# T-11_Version_7.net
KiCad netlist of a schematic drawn in EAGLE
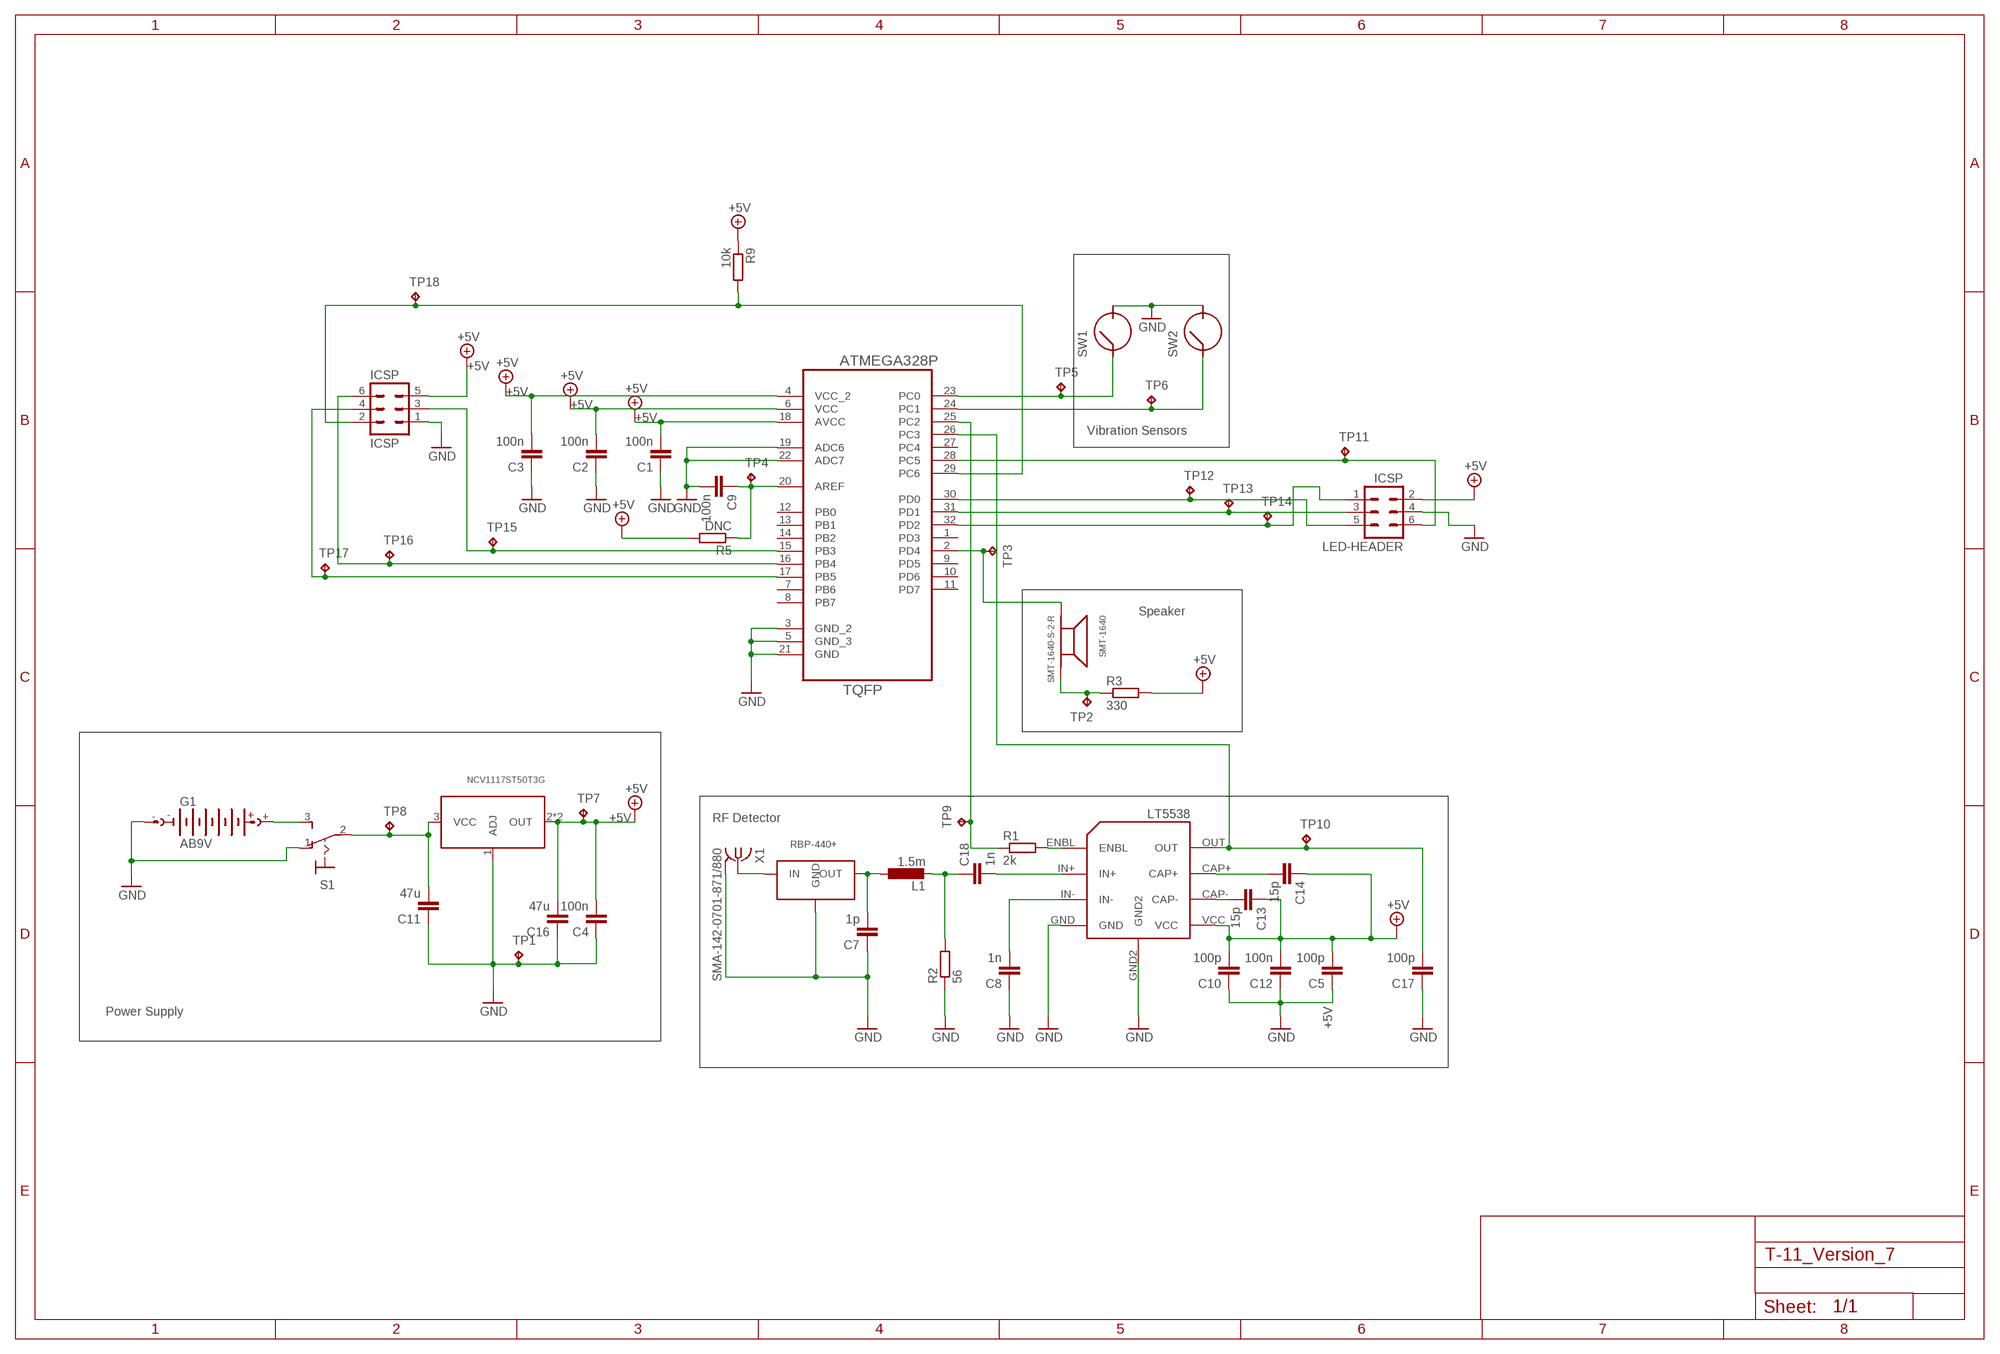
[diagram p0: schematic, sheet 1]

(export (version "E")
  (design (tool "Eeschema 10.0.6"))
  (components
    (comp (ref "C1")
      (value "100n")
      (footprint "eagle-import:C0805")
      (libsource (lib "eagle-import") (part "C-EUC0805"))
    )
    (comp (ref "C2")
      (value "100n")
      (footprint "eagle-import:C0805")
      (libsource (lib "eagle-import") (part "C-EUC0805"))
    )
    (comp (ref "C3")
      (value "100n")
      (footprint "eagle-import:C0805")
      (libsource (lib "eagle-import") (part "C-EUC0805"))
    )
    (comp (ref "C4")
      (value "100n")
      (footprint "eagle-import:C0805")
      (libsource (lib "eagle-import") (part "C-EUC0805"))
    )
    (comp (ref "C5")
      (value "100p")
      (footprint "eagle-import:C0805")
      (libsource (lib "eagle-import") (part "C-EUC0805"))
    )
    (comp (ref "C7")
      (value "1p")
      (footprint "eagle-import:C0805")
      (libsource (lib "eagle-import") (part "C-EUC0805"))
    )
    (comp (ref "C8")
      (value "1n")
      (footprint "eagle-import:C0805")
      (libsource (lib "eagle-import") (part "C-EUC0805"))
    )
    (comp (ref "C9")
      (value "100n")
      (footprint "eagle-import:C0805")
      (libsource (lib "eagle-import") (part "C-EUC0805"))
    )
    (comp (ref "C10")
      (value "100p")
      (footprint "eagle-import:C0805")
      (libsource (lib "eagle-import") (part "C-EUC0805"))
    )
    (comp (ref "C11")
      (value "47u")
      (footprint "eagle-import:C0805")
      (libsource (lib "eagle-import") (part "C-EUC0805"))
    )
    (comp (ref "C12")
      (value "100n")
      (footprint "eagle-import:C0805")
      (libsource (lib "eagle-import") (part "C-EUC0805"))
    )
    (comp (ref "C13")
      (value "15p")
      (footprint "eagle-import:C0805")
      (libsource (lib "eagle-import") (part "C-EUC0805"))
    )
    (comp (ref "C14")
      (value "15p")
      (footprint "eagle-import:C0805")
      (libsource (lib "eagle-import") (part "C-EUC0805"))
    )
    (comp (ref "C16")
      (value "47u")
      (footprint "eagle-import:C0805")
      (libsource (lib "eagle-import") (part "C-EUC0805"))
    )
    (comp (ref "C17")
      (value "100p")
      (footprint "eagle-import:C0805")
      (libsource (lib "eagle-import") (part "C-EUC0805"))
    )
    (comp (ref "C18")
      (value "1n")
      (footprint "eagle-import:C0805")
      (libsource (lib "eagle-import") (part "C-EUC0805"))
    )
    (comp (ref "G1")
      (value "AB9V")
      (footprint "eagle-import:AB9V")
      (libsource (lib "eagle-import") (part "AB9V"))
    )
    (comp (ref "ICSP")
      (value "ICSP")
      (footprint "eagle-import:MA03-2")
      (libsource (lib "eagle-import") (part "MA03-2"))
    )
    (comp (ref "L1")
      (value "1.5m")
      (footprint "eagle-import:L2825P")
      (libsource (lib "eagle-import") (part "L-EUL2825P"))
    )
    (comp (ref "LED-HEADER")
      (value "ICSP")
      (footprint "eagle-import:MA03-2")
      (libsource (lib "eagle-import") (part "MA03-2"))
    )
    (comp (ref "LT5538")
      (value "LT5538")
      (footprint "eagle-import:LT5538")
      (libsource (lib "eagle-import") (part "LT5538"))
    )
    (comp (ref "NVC1")
      (value "NCV1117ST50T3G")
      (footprint "eagle-import:SOT223")
      (libsource (lib "eagle-import") (part "NCV1117ST50T3G"))
    )
    (comp (ref "R1")
      (value "2k")
      (footprint "eagle-import:R0805")
      (libsource (lib "eagle-import") (part "R-EU_R0805"))
    )
    (comp (ref "R2")
      (value "56")
      (footprint "eagle-import:R0805")
      (libsource (lib "eagle-import") (part "R-EU_R0805"))
    )
    (comp (ref "R3")
      (value "330")
      (footprint "eagle-import:R0805")
      (libsource (lib "eagle-import") (part "R-EU_R0805"))
    )
    (comp (ref "R5")
      (value "DNC")
      (footprint "eagle-import:R0805")
      (libsource (lib "eagle-import") (part "R-EU_R0805"))
    )
    (comp (ref "R9")
      (value "10k")
      (footprint "eagle-import:R0805")
      (libsource (lib "eagle-import") (part "R-EU_R0805"))
    )
    (comp (ref "RBP-440+")
      (value "RBP-440+")
      (footprint "eagle-import:GP731")
      (libsource (lib "eagle-import") (part "RBP-440+"))
    )
    (comp (ref "S1")
      (value "320-916")
      (footprint "eagle-import:320-916")
      (libsource (lib "eagle-import") (part "320-916"))
    )
    (comp (ref "SMT-1640")
      (value "SMT-1640-S-2-R")
      (footprint "eagle-import:SMT-1640")
      (libsource (lib "eagle-import") (part "SMT-1640-S-2-R"))
    )
    (comp (ref "SW1")
      (value "SW-1801X")
      (footprint "eagle-import:SW-1801X")
      (libsource (lib "eagle-import") (part "SW-1801X"))
    )
    (comp (ref "SW2")
      (value "SW-1801X")
      (footprint "eagle-import:SW-1801X")
      (libsource (lib "eagle-import") (part "SW-1801X"))
    )
    (comp (ref "TP1")
      (value "TPTP10R")
      (footprint "eagle-import:TP10R")
      (libsource (lib "eagle-import") (part "TPTP10R"))
    )
    (comp (ref "TP2")
      (value "TPTP10R")
      (footprint "eagle-import:TP10R")
      (libsource (lib "eagle-import") (part "TPTP10R"))
    )
    (comp (ref "TP3")
      (value "TPTP10R")
      (footprint "eagle-import:TP10R")
      (libsource (lib "eagle-import") (part "TPTP10R"))
    )
    (comp (ref "TP4")
      (value "TPTP10R")
      (footprint "eagle-import:TP10R")
      (libsource (lib "eagle-import") (part "TPTP10R"))
    )
    (comp (ref "TP5")
      (value "TPTP10R")
      (footprint "eagle-import:TP10R")
      (libsource (lib "eagle-import") (part "TPTP10R"))
    )
    (comp (ref "TP6")
      (value "TPTP10R")
      (footprint "eagle-import:TP10R")
      (libsource (lib "eagle-import") (part "TPTP10R"))
    )
    (comp (ref "TP7")
      (value "TPTP10R")
      (footprint "eagle-import:TP10R")
      (libsource (lib "eagle-import") (part "TPTP10R"))
    )
    (comp (ref "TP8")
      (value "TPTP10R")
      (footprint "eagle-import:TP10R")
      (libsource (lib "eagle-import") (part "TPTP10R"))
    )
    (comp (ref "TP9")
      (value "TPTP10R")
      (footprint "eagle-import:TP10R")
      (libsource (lib "eagle-import") (part "TPTP10R"))
    )
    (comp (ref "TP10")
      (value "TPTP10R")
      (footprint "eagle-import:TP10R")
      (libsource (lib "eagle-import") (part "TPTP10R"))
    )
    (comp (ref "TP11")
      (value "TPTP10R")
      (footprint "eagle-import:TP10R")
      (libsource (lib "eagle-import") (part "TPTP10R"))
    )
    (comp (ref "TP12")
      (value "TPTP10R")
      (footprint "eagle-import:TP10R")
      (libsource (lib "eagle-import") (part "TPTP10R"))
    )
    (comp (ref "TP13")
      (value "TPTP10R")
      (footprint "eagle-import:TP10R")
      (libsource (lib "eagle-import") (part "TPTP10R"))
    )
    (comp (ref "TP14")
      (value "TPTP10R")
      (footprint "eagle-import:TP10R")
      (libsource (lib "eagle-import") (part "TPTP10R"))
    )
    (comp (ref "TP15")
      (value "TPTP10R")
      (footprint "eagle-import:TP10R")
      (libsource (lib "eagle-import") (part "TPTP10R"))
    )
    (comp (ref "TP16")
      (value "TPTP10R")
      (footprint "eagle-import:TP10R")
      (libsource (lib "eagle-import") (part "TPTP10R"))
    )
    (comp (ref "TP17")
      (value "TPTP10R")
      (footprint "eagle-import:TP10R")
      (libsource (lib "eagle-import") (part "TPTP10R"))
    )
    (comp (ref "TP18")
      (value "TPTP10R")
      (footprint "eagle-import:TP10R")
      (libsource (lib "eagle-import") (part "TPTP10R"))
    )
    (comp (ref "U1")
      (value "ATMEGA328P-AU")
      (footprint "eagle-import:QFP80P900X900X120-32N")
      (libsource (lib "eagle-import") (part "ATMEGA328P-AU"))
    )
    (comp (ref "X1")
      (value "SMA-142-0701-871/880")
      (footprint "eagle-import:SMA-142-0701-871")
      (fields (field (name "MF") "JOHNSON COMPONENTS") (field (name "MPN") "142-0701-871"))
      (libsource (lib "eagle-import") (part "SMA-142-0701-871/880"))
    )
  )
  (nets
    (net (code "1") (name "+5V") (class "Default")
      (node (ref "C1") (pin "2") (pinfunction "2_2") (pintype "passive"))
      (node (ref "C10") (pin "2") (pinfunction "2_2") (pintype "passive"))
      (node (ref "C12") (pin "2") (pinfunction "2_2") (pintype "passive"))
      (node (ref "C13") (pin "1") (pinfunction "1_1") (pintype "passive"))
      (node (ref "C14") (pin "1") (pinfunction "1_1") (pintype "passive"))
      (node (ref "C16") (pin "2") (pinfunction "2_2") (pintype "passive"))
      (node (ref "C2") (pin "2") (pinfunction "2_2") (pintype "passive"))
      (node (ref "C3") (pin "2") (pinfunction "2_2") (pintype "passive"))
      (node (ref "C4") (pin "2") (pinfunction "2_2") (pintype "passive"))
      (node (ref "C5") (pin "2") (pinfunction "2_2") (pintype "passive"))
      (node (ref "ICSP") (pin "5") (pinfunction "5_5") (pintype "passive"))
      (node (ref "LED-HEADER") (pin "2") (pinfunction "2_2") (pintype "passive"))
      (node (ref "LT5538") (pin "VCC") (pinfunction "VCC_VCC") (pintype "power_in"))
      (node (ref "NVC1") (pin "2") (pinfunction "OUT_2") (pintype "power_in"))
      (node (ref "NVC1") (pin "4") (pinfunction "OUT_4") (pintype "power_in"))
      (node (ref "R3") (pin "2") (pinfunction "2_2") (pintype "passive"))
      (node (ref "R5") (pin "2") (pinfunction "2_2") (pintype "passive"))
      (node (ref "R9") (pin "1") (pinfunction "1_1") (pintype "passive"))
      (node (ref "TP7") (pin "TP") (pinfunction "TP_TP") (pintype "input"))
      (node (ref "U1") (pin "18") (pinfunction "AVCC_18") (pintype "power_in"))
      (node (ref "U1") (pin "4") (pinfunction "VCC_2_4") (pintype "power_in"))
      (node (ref "U1") (pin "6") (pinfunction "VCC_6") (pintype "power_in"))
    )
    (net (code "2") (name "GND") (class "Default")
      (node (ref "C1") (pin "1") (pinfunction "1_1") (pintype "passive"))
      (node (ref "C10") (pin "1") (pinfunction "1_1") (pintype "passive"))
      (node (ref "C11") (pin "1") (pinfunction "1_1") (pintype "passive"))
      (node (ref "C12") (pin "1") (pinfunction "1_1") (pintype "passive"))
      (node (ref "C16") (pin "1") (pinfunction "1_1") (pintype "passive"))
      (node (ref "C17") (pin "1") (pinfunction "1_1") (pintype "passive"))
      (node (ref "C2") (pin "1") (pinfunction "1_1") (pintype "passive"))
      (node (ref "C3") (pin "1") (pinfunction "1_1") (pintype "passive"))
      (node (ref "C4") (pin "1") (pinfunction "1_1") (pintype "passive"))
      (node (ref "C5") (pin "1") (pinfunction "1_1") (pintype "passive"))
      (node (ref "C7") (pin "1") (pinfunction "1_1") (pintype "passive"))
      (node (ref "C8") (pin "1") (pinfunction "1_1") (pintype "passive"))
      (node (ref "C9") (pin "2") (pinfunction "2_2") (pintype "passive"))
      (node (ref "G1") (pin "-") (pinfunction "-_-") (pintype "passive"))
      (node (ref "ICSP") (pin "1") (pinfunction "1_1") (pintype "passive"))
      (node (ref "LED-HEADER") (pin "4") (pinfunction "4_4") (pintype "passive"))
      (node (ref "LT5538") (pin "GND") (pinfunction "GND_GND") (pintype "power_in"))
      (node (ref "LT5538") (pin "GND2") (pinfunction "GND2_GND2") (pintype "bidirectional"))
      (node (ref "NVC1") (pin "1") (pinfunction "ADJ_1") (pintype "bidirectional"))
      (node (ref "R2") (pin "1") (pinfunction "1_1") (pintype "passive"))
      (node (ref "RBP-440+") (pin "1") (pinfunction "GND_1") (pintype "power_in"))
      (node (ref "RBP-440+") (pin "3") (pinfunction "GND_3") (pintype "power_in"))
      (node (ref "RBP-440+") (pin "4") (pinfunction "GND_4") (pintype "power_in"))
      (node (ref "RBP-440+") (pin "5") (pinfunction "GND_5") (pintype "power_in"))
      (node (ref "RBP-440+") (pin "7") (pinfunction "GND_7") (pintype "power_in"))
      (node (ref "RBP-440+") (pin "8") (pinfunction "GND_8") (pintype "power_in"))
      (node (ref "S1") (pin "1") (pinfunction "O_1") (pintype "passive"))
      (node (ref "SW1") (pin "P$2") (pinfunction "P$2_P$2") (pintype "bidirectional"))
      (node (ref "SW2") (pin "P$2") (pinfunction "P$2_P$2") (pintype "bidirectional"))
      (node (ref "TP1") (pin "TP") (pinfunction "TP_TP") (pintype "input"))
      (node (ref "U1") (pin "19") (pinfunction "ADC6_19") (pintype "input"))
      (node (ref "U1") (pin "21") (pinfunction "GND_21") (pintype "passive"))
      (node (ref "U1") (pin "22") (pinfunction "ADC7_22") (pintype "input"))
      (node (ref "U1") (pin "3") (pinfunction "GND_2_3") (pintype "passive"))
      (node (ref "U1") (pin "5") (pinfunction "GND_3_5") (pintype "passive"))
      (node (ref "X1") (pin "2@1") (pinfunction "2_2@1") (pintype "passive"))
      (node (ref "X1") (pin "2@2") (pinfunction "2_2@2") (pintype "passive"))
      (node (ref "X1") (pin "2@3") (pinfunction "2_2@3") (pintype "passive"))
      (node (ref "X1") (pin "2@4") (pinfunction "2_2@4") (pintype "passive"))
    )
    (net (code "3") (name "Net-(C8-Pad2)") (class "Default")
      (node (ref "C8") (pin "2") (pinfunction "2_2") (pintype "passive"))
      (node (ref "LT5538") (pin "IN-") (pinfunction "IN-_IN-") (pintype "bidirectional"))
    )
    (net (code "4") (name "Net-(C13-Pad2)") (class "Default")
      (node (ref "C13") (pin "2") (pinfunction "2_2") (pintype "passive"))
      (node (ref "LT5538") (pin "CAP-") (pinfunction "CAP-_CAP-") (pintype "bidirectional"))
    )
    (net (code "5") (name "Net-(C14-Pad2)") (class "Default")
      (node (ref "C14") (pin "2") (pinfunction "2_2") (pintype "passive"))
      (node (ref "LT5538") (pin "CAP+") (pinfunction "CAP+_CAP+") (pintype "bidirectional"))
    )
    (net (code "6") (name "Net-(C18-Pad1)") (class "Default")
      (node (ref "C18") (pin "1") (pinfunction "1_1") (pintype "passive"))
      (node (ref "L1") (pin "2") (pinfunction "2_2") (pintype "passive"))
      (node (ref "R2") (pin "2") (pinfunction "2_2") (pintype "passive"))
    )
    (net (code "7") (name "Net-(C18-Pad2)") (class "Default")
      (node (ref "C18") (pin "2") (pinfunction "2_2") (pintype "passive"))
      (node (ref "LT5538") (pin "IN+") (pinfunction "IN+_IN+") (pintype "bidirectional"))
    )
    (net (code "8") (name "Net-(LT5538-PadENBL)") (class "Default")
      (node (ref "LT5538") (pin "ENBL") (pinfunction "ENBL_ENBL") (pintype "bidirectional"))
      (node (ref "R1") (pin "2") (pinfunction "2_2") (pintype "passive"))
    )
    (net (code "9") (name "Net-(NVC1-VCC)") (class "Default")
      (node (ref "C11") (pin "2") (pinfunction "2_2") (pintype "passive"))
      (node (ref "NVC1") (pin "3") (pinfunction "VCC_3") (pintype "input"))
      (node (ref "S1") (pin "2") (pinfunction "P_2") (pintype "passive"))
      (node (ref "TP8") (pin "TP") (pinfunction "TP_TP") (pintype "input"))
    )
    (net (code "10") (name "Net-(RBP-440+-IN)") (class "Default")
      (node (ref "RBP-440+") (pin "2") (pinfunction "IN_2") (pintype "bidirectional"))
      (node (ref "X1") (pin "1") (pinfunction "1_1") (pintype "passive"))
    )
    (net (code "11") (name "Net-(RBP-440+-OUT)") (class "Default")
      (node (ref "C7") (pin "2") (pinfunction "2_2") (pintype "passive"))
      (node (ref "L1") (pin "1") (pinfunction "1_1") (pintype "passive"))
      (node (ref "RBP-440+") (pin "6") (pinfunction "OUT_6") (pintype "output"))
    )
    (net (code "12") (name "Net-(S1-S)") (class "Default")
      (node (ref "G1") (pin "+") (pinfunction "+_+") (pintype "passive"))
      (node (ref "S1") (pin "3") (pinfunction "S_3") (pintype "passive"))
    )
    (net (code "13") (name "Net-(SMT-1640-IN)") (class "Default")
      (node (ref "SMT-1640") (pin "P$2") (pinfunction "IN_P$2") (pintype "bidirectional"))
      (node (ref "TP3") (pin "TP") (pinfunction "TP_TP") (pintype "input"))
      (node (ref "U1") (pin "2") (pinfunction "PD4_2") (pintype "bidirectional"))
    )
    (net (code "14") (name "Net-(SMT-1640-OUT)") (class "Default")
      (node (ref "R3") (pin "1") (pinfunction "1_1") (pintype "passive"))
      (node (ref "SMT-1640") (pin "P$1") (pinfunction "OUT_P$1") (pintype "bidirectional"))
      (node (ref "TP2") (pin "TP") (pinfunction "TP_TP") (pintype "input"))
    )
    (net (code "15") (name "Net-(U1-AREF)") (class "Default")
      (node (ref "C9") (pin "1") (pinfunction "1_1") (pintype "passive"))
      (node (ref "R5") (pin "1") (pinfunction "1_1") (pintype "passive"))
      (node (ref "TP4") (pin "TP") (pinfunction "TP_TP") (pintype "input"))
      (node (ref "U1") (pin "20") (pinfunction "AREF_20") (pintype "input"))
    )
    (net (code "16") (name "Net-(U1-PB3)") (class "Default")
      (node (ref "ICSP") (pin "3") (pinfunction "3_3") (pintype "passive"))
      (node (ref "TP15") (pin "TP") (pinfunction "TP_TP") (pintype "input"))
      (node (ref "U1") (pin "15") (pinfunction "PB3_15") (pintype "bidirectional"))
    )
    (net (code "17") (name "Net-(U1-PB4)") (class "Default")
      (node (ref "ICSP") (pin "6") (pinfunction "6_6") (pintype "passive"))
      (node (ref "TP16") (pin "TP") (pinfunction "TP_TP") (pintype "input"))
      (node (ref "U1") (pin "16") (pinfunction "PB4_16") (pintype "bidirectional"))
    )
    (net (code "18") (name "Net-(U1-PB5)") (class "Default")
      (node (ref "ICSP") (pin "4") (pinfunction "4_4") (pintype "passive"))
      (node (ref "TP17") (pin "TP") (pinfunction "TP_TP") (pintype "input"))
      (node (ref "U1") (pin "17") (pinfunction "PB5_17") (pintype "bidirectional"))
    )
    (net (code "19") (name "Net-(U1-PC0)") (class "Default")
      (node (ref "SW1") (pin "P$1") (pinfunction "P$1_P$1") (pintype "bidirectional"))
      (node (ref "TP5") (pin "TP") (pinfunction "TP_TP") (pintype "input"))
      (node (ref "U1") (pin "23") (pinfunction "PC0_23") (pintype "bidirectional"))
    )
    (net (code "20") (name "Net-(U1-PC1)") (class "Default")
      (node (ref "SW2") (pin "P$1") (pinfunction "P$1_P$1") (pintype "bidirectional"))
      (node (ref "TP6") (pin "TP") (pinfunction "TP_TP") (pintype "input"))
      (node (ref "U1") (pin "24") (pinfunction "PC1_24") (pintype "bidirectional"))
    )
    (net (code "21") (name "Net-(U1-PC2)") (class "Default")
      (node (ref "R1") (pin "1") (pinfunction "1_1") (pintype "passive"))
      (node (ref "TP9") (pin "TP") (pinfunction "TP_TP") (pintype "input"))
      (node (ref "U1") (pin "25") (pinfunction "PC2_25") (pintype "bidirectional"))
    )
    (net (code "22") (name "Net-(U1-PC3)") (class "Default")
      (node (ref "C17") (pin "2") (pinfunction "2_2") (pintype "passive"))
      (node (ref "LT5538") (pin "OUT") (pinfunction "OUT_OUT") (pintype "output"))
      (node (ref "TP10") (pin "TP") (pinfunction "TP_TP") (pintype "input"))
      (node (ref "U1") (pin "26") (pinfunction "PC3_26") (pintype "bidirectional"))
    )
    (net (code "23") (name "Net-(U1-PC5)") (class "Default")
      (node (ref "LED-HEADER") (pin "6") (pinfunction "6_6") (pintype "passive"))
      (node (ref "TP11") (pin "TP") (pinfunction "TP_TP") (pintype "input"))
      (node (ref "U1") (pin "28") (pinfunction "PC5_28") (pintype "bidirectional"))
    )
    (net (code "24") (name "Net-(U1-PC6)") (class "Default")
      (node (ref "ICSP") (pin "2") (pinfunction "2_2") (pintype "passive"))
      (node (ref "R9") (pin "2") (pinfunction "2_2") (pintype "passive"))
      (node (ref "TP18") (pin "TP") (pinfunction "TP_TP") (pintype "input"))
      (node (ref "U1") (pin "29") (pinfunction "PC6_29") (pintype "bidirectional"))
    )
    (net (code "25") (name "Net-(U1-PD0)") (class "Default")
      (node (ref "LED-HEADER") (pin "5") (pinfunction "5_5") (pintype "passive"))
      (node (ref "TP12") (pin "TP") (pinfunction "TP_TP") (pintype "input"))
      (node (ref "U1") (pin "30") (pinfunction "PD0_30") (pintype "bidirectional"))
    )
    (net (code "26") (name "Net-(U1-PD1)") (class "Default")
      (node (ref "LED-HEADER") (pin "3") (pinfunction "3_3") (pintype "passive"))
      (node (ref "TP13") (pin "TP") (pinfunction "TP_TP") (pintype "input"))
      (node (ref "U1") (pin "31") (pinfunction "PD1_31") (pintype "bidirectional"))
    )
    (net (code "27") (name "Net-(U1-PD2)") (class "Default")
      (node (ref "LED-HEADER") (pin "1") (pinfunction "1_1") (pintype "passive"))
      (node (ref "TP14") (pin "TP") (pinfunction "TP_TP") (pintype "input"))
      (node (ref "U1") (pin "32") (pinfunction "PD2_32") (pintype "bidirectional"))
    )
    (net (code "28") (name "unconnected-(U1-PB0-Pad12)") (class "Default")
      (node (ref "U1") (pin "12") (pinfunction "PB0_12") (pintype "bidirectional"))
    )
    (net (code "29") (name "unconnected-(U1-PB1-Pad13)") (class "Default")
      (node (ref "U1") (pin "13") (pinfunction "PB1_13") (pintype "bidirectional"))
    )
    (net (code "30") (name "unconnected-(U1-PB2-Pad14)") (class "Default")
      (node (ref "U1") (pin "14") (pinfunction "PB2_14") (pintype "bidirectional"))
    )
    (net (code "31") (name "unconnected-(U1-PB6-Pad7)") (class "Default")
      (node (ref "U1") (pin "7") (pinfunction "PB6_7") (pintype "bidirectional"))
    )
    (net (code "32") (name "unconnected-(U1-PB7-Pad8)") (class "Default")
      (node (ref "U1") (pin "8") (pinfunction "PB7_8") (pintype "bidirectional"))
    )
    (net (code "33") (name "unconnected-(U1-PC4-Pad27)") (class "Default")
      (node (ref "U1") (pin "27") (pinfunction "PC4_27") (pintype "bidirectional"))
    )
    (net (code "34") (name "unconnected-(U1-PD3-Pad1)") (class "Default")
      (node (ref "U1") (pin "1") (pinfunction "PD3_1") (pintype "bidirectional"))
    )
    (net (code "35") (name "unconnected-(U1-PD5-Pad9)") (class "Default")
      (node (ref "U1") (pin "9") (pinfunction "PD5_9") (pintype "bidirectional"))
    )
    (net (code "36") (name "unconnected-(U1-PD6-Pad10)") (class "Default")
      (node (ref "U1") (pin "10") (pinfunction "PD6_10") (pintype "bidirectional"))
    )
    (net (code "37") (name "unconnected-(U1-PD7-Pad11)") (class "Default")
      (node (ref "U1") (pin "11") (pinfunction "PD7_11") (pintype "bidirectional"))
    )
  )
)
